# PIC.net
KiCad netlist of a schematic drawn in Altium Designer
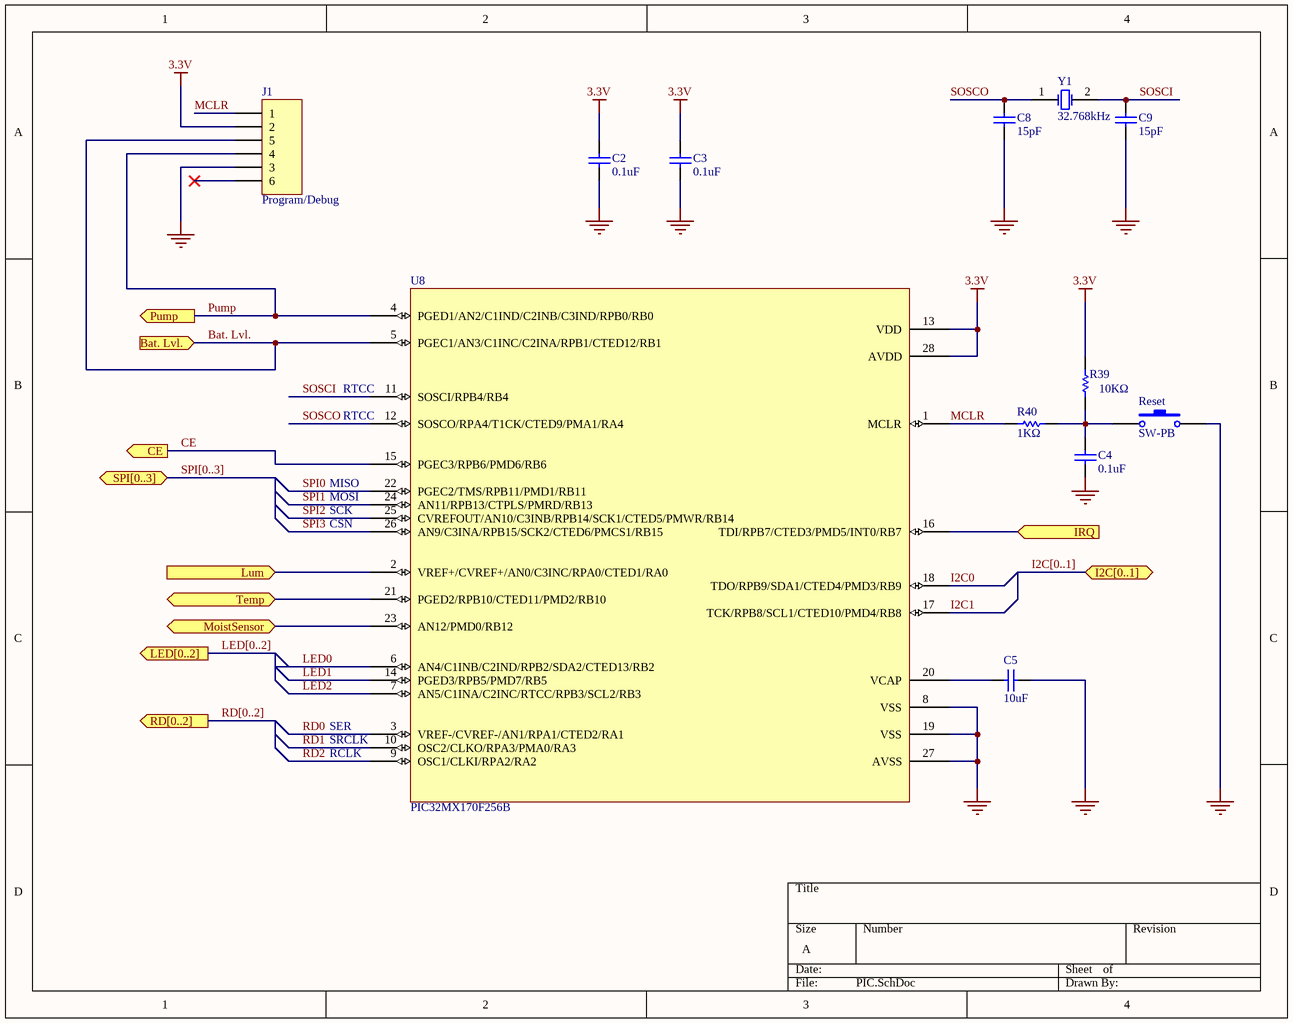
[diagram p0: PIC.SchDoc]

(export (version "E")
  (design (tool "Eeschema 10.0.6"))
  (components
    (comp (ref "C2")
      (value "0.1uF")
      (footprint "C0603")
      (description "Capacitor")
      (fields (field (name "MANUFACTURER") "MURATA") (field (name "PUBLISHER") "Altium Limited"))
      (libsource (lib "Miscellaneous Devices") (part "Cap"))
    )
    (comp (ref "C3")
      (value "0.1uF")
      (footprint "C0603")
      (description "Capacitor")
      (fields (field (name "MANUFACTURER") "MURATA") (field (name "PUBLISHER") "Altium Limited"))
      (libsource (lib "Miscellaneous Devices") (part "Cap"))
    )
    (comp (ref "C4")
      (value "0.1uF")
      (footprint "C0603")
      (description "Capacitor")
      (fields (field (name "MANUFACTURER") "MURATA") (field (name "PUBLISHER") "Altium Limited"))
      (libsource (lib "Miscellaneous Devices") (part "Cap"))
    )
    (comp (ref "C5")
      (value "10uF")
      (footprint "C0603")
      (description "Capacitor")
      (fields (field (name "MANUFACTURER") "MURATA") (field (name "PUBLISHER") "Altium Limited"))
      (libsource (lib "Miscellaneous Devices") (part "Cap"))
    )
    (comp (ref "C8")
      (value "15pF")
      (footprint "C0603")
      (description "Capacitor")
      (fields (field (name "MANUFACTURER") "MURATA") (field (name "PUBLISHER") "Altium Limited"))
      (libsource (lib "Miscellaneous Devices") (part "Cap"))
    )
    (comp (ref "C9")
      (value "15pF")
      (footprint "C0603")
      (description "Capacitor")
      (fields (field (name "MANUFACTURER") "MURATA") (field (name "PUBLISHER") "Altium Limited"))
      (libsource (lib "Miscellaneous Devices") (part "Cap"))
    )
    (comp (ref "J1")
      (value "Program/Debug")
      (footprint "HDR1X6")
      (description "Header, 6-Pin")
      (fields (field (name "PUBLISHER") "Altium Limited"))
      (libsource (lib "Miscellaneous Connectors") (part "Header 6"))
    )
    (comp (ref "R39")
      (value "10KΩ")
      (footprint "R0603")
      (description "Resistor")
      (fields (field (name "MANUFACTURER") "MULTICOMP") (field (name "PUBLISHER") "Altium Limited"))
      (libsource (lib "Miscellaneous Devices") (part "Res1"))
    )
    (comp (ref "R40")
      (value "1KΩ")
      (footprint "R0603")
      (description "Resistor")
      (fields (field (name "MANUFACTURER") "MULTICOMP") (field (name "PUBLISHER") "Altium Limited"))
      (libsource (lib "Miscellaneous Devices") (part "Res1"))
    )
    (comp (ref "Reset")
      (value "SW-PB")
      (footprint "Reset")
      (description "Switch")
      (fields
        (field (name "MANUFACTURER") "ALCOSWITCH - TE CONNECTIVITY")
        (field (name "PUBLISHER") "Altium Limited")
      )
      (libsource (lib "Miscellaneous Devices") (part "SW-PB"))
    )
    (comp (ref "U8")
      (value "PIC32MX170F256B")
      (footprint "PIC32MX170F256B")
      (description "Pic")
      (fields (field (name "MANUFACTURER") "MICROCHIP"))
      (libsource (lib "Electroplant") (part "PIC32MX170F256B"))
    )
    (comp (ref "Y1")
      (value "32.768kHz")
      (footprint "XTAL")
      (description "Crystal Oscillator")
      (fields (field (name "MANUFACTURER") "ABRACON") (field (name "PUBLISHER") "Altium Limited"))
      (libsource (lib "Miscellaneous Devices") (part "XTAL"))
    )
  )
  (nets
    (net (code "1") (name "/Bat. Lvl.") (class "Default")
      (node (ref "J1") (pin "5") (pinfunction "5_5") (pintype "passive"))
      (node (ref "U8") (pin "5") (pinfunction "PGEC1/AN3/C1INC/C2INA/RPB1/CTED12/RB1_5") (pintype "bidirectional"))
    )
    (net (code "2") (name "/CE") (class "Default")
      (node (ref "U8") (pin "15") (pinfunction "PGEC3/RPB6/PMD6/RB6_15") (pintype "bidirectional"))
    )
    (net (code "3") (name "/I2C0") (class "Default")
      (node (ref "U8") (pin "18") (pinfunction "TDO/RPB9/SDA1/CTED4/PMD3/RB9_18") (pintype "bidirectional"))
    )
    (net (code "4") (name "/I2C1") (class "Default")
      (node (ref "U8") (pin "17") (pinfunction "TCK/RPB8/SCL1/CTED10/PMD4/RB8_17") (pintype "bidirectional"))
    )
    (net (code "6") (name "/IRQ") (class "Default")
      (node (ref "U8") (pin "16") (pinfunction "TDI/RPB7/CTED3/PMD5/INT0/RB7_16") (pintype "bidirectional"))
    )
    (net (code "7") (name "/LED0") (class "Default")
      (node (ref "U8") (pin "6") (pinfunction "AN4/C1INB/C2IND/RPB2/SDA2/CTED13/RB2_6") (pintype "bidirectional"))
    )
    (net (code "8") (name "/LED1") (class "Default")
      (node (ref "U8") (pin "14") (pinfunction "PGED3/RPB5/PMD7/RB5_14") (pintype "bidirectional"))
    )
    (net (code "9") (name "/LED2") (class "Default")
      (node (ref "U8") (pin "7") (pinfunction "AN5/C1INA/C2INC/RTCC/RPB3/SCL2/RB3_7") (pintype "bidirectional"))
    )
    (net (code "11") (name "/Lum") (class "Default")
      (node (ref "U8") (pin "2") (pinfunction "VREF+/CVREF+/AN0/C3INC/RPA0/CTED1/RA0_2") (pintype "bidirectional"))
    )
    (net (code "12") (name "/MCLR") (class "Default")
      (node (ref "J1") (pin "1") (pinfunction "1_1") (pintype "passive"))
      (node (ref "R40") (pin "2") (pinfunction "2_2") (pintype "passive"))
      (node (ref "U8") (pin "1") (pinfunction "MCLR_1") (pintype "bidirectional"))
    )
    (net (code "13") (name "/MoistSensor") (class "Default")
      (node (ref "U8") (pin "23") (pinfunction "AN12/PMD0/RB12_23") (pintype "bidirectional"))
    )
    (net (code "14") (name "/Pump") (class "Default")
      (node (ref "J1") (pin "4") (pinfunction "4_4") (pintype "passive"))
      (node (ref "U8") (pin "4") (pinfunction "PGED1/AN2/C1IND/C2INB/C3IND/RPB0/RB0_4") (pintype "bidirectional"))
    )
    (net (code "15") (name "/RD0") (class "Default")
      (node (ref "U8") (pin "3") (pinfunction "VREF-/CVREF-/AN1/RPA1/CTED2/RA1_3") (pintype "bidirectional"))
    )
    (net (code "16") (name "/RD1") (class "Default")
      (node (ref "U8") (pin "10") (pinfunction "OSC2/CLKO/RPA3/PMA0/RA3_10") (pintype "bidirectional"))
    )
    (net (code "17") (name "/RD2") (class "Default")
      (node (ref "U8") (pin "9") (pinfunction "OSC1/CLKI/RPA2/RA2_9") (pintype "bidirectional"))
    )
    (net (code "19") (name "/SOSCI") (class "Default")
      (node (ref "C9") (pin "2") (pinfunction "2_2") (pintype "passive"))
      (node (ref "U8") (pin "11") (pinfunction "SOSCI/RPB4/RB4_11") (pintype "bidirectional"))
      (node (ref "Y1") (pin "2") (pinfunction "OSC2_2") (pintype "passive"))
    )
    (net (code "20") (name "/SOSCO") (class "Default")
      (node (ref "C8") (pin "2") (pinfunction "2_2") (pintype "passive"))
      (node (ref "U8") (pin "12") (pinfunction "SOSCO/RPA4/T1CK/CTED9/PMA1/RA4_12") (pintype "bidirectional"))
      (node (ref "Y1") (pin "1") (pinfunction "OSC1_1") (pintype "passive"))
    )
    (net (code "21") (name "/SPI0") (class "Default")
      (node (ref "U8") (pin "22") (pinfunction "PGEC2/TMS/RPB11/PMD1/RB11_22") (pintype "bidirectional"))
    )
    (net (code "22") (name "/SPI1") (class "Default")
      (node (ref "U8") (pin "24") (pinfunction "AN11/RPB13/CTPLS/PMRD/RB13_24") (pintype "bidirectional"))
    )
    (net (code "23") (name "/SPI2") (class "Default")
      (node (ref "U8") (pin "25") (pinfunction "CVREFOUT/AN10/C3INB/RPB14/SCK1/CTED5/PMWR/RB14_25") (pintype "bidirectional"))
    )
    (net (code "24") (name "/SPI3") (class "Default")
      (node (ref "U8") (pin "26") (pinfunction "AN9/C3INA/RPB15/SCK2/CTED6/PMCS1/RB15_26") (pintype "bidirectional"))
    )
    (net (code "26") (name "/Temp") (class "Default")
      (node (ref "U8") (pin "21") (pinfunction "PGED2/RPB10/CTED11/PMD2/RB10_21") (pintype "bidirectional"))
    )
    (net (code "27") (name "3.3V") (class "Default")
      (node (ref "C2") (pin "2") (pinfunction "2_2") (pintype "passive"))
      (node (ref "C3") (pin "2") (pinfunction "2_2") (pintype "passive"))
      (node (ref "J1") (pin "2") (pinfunction "2_2") (pintype "passive"))
      (node (ref "R39") (pin "2") (pinfunction "2_2") (pintype "passive"))
      (node (ref "U8") (pin "13") (pinfunction "VDD_13") (pintype "power_in"))
      (node (ref "U8") (pin "28") (pinfunction "AVDD_28") (pintype "power_in"))
    )
    (net (code "28") (name "GND") (class "Default")
      (node (ref "C2") (pin "1") (pinfunction "1_1") (pintype "passive"))
      (node (ref "C3") (pin "1") (pinfunction "1_1") (pintype "passive"))
      (node (ref "C4") (pin "1") (pinfunction "1_1") (pintype "passive"))
      (node (ref "C5") (pin "2") (pinfunction "2_2") (pintype "passive"))
      (node (ref "C8") (pin "1") (pinfunction "1_1") (pintype "passive"))
      (node (ref "C9") (pin "1") (pinfunction "1_1") (pintype "passive"))
      (node (ref "J1") (pin "3") (pinfunction "3_3") (pintype "passive"))
      (node (ref "Reset") (pin "2") (pinfunction "2_2") (pintype "passive"))
      (node (ref "U8") (pin "19") (pinfunction "VSS_19") (pintype "power_in"))
      (node (ref "U8") (pin "27") (pinfunction "AVSS_27") (pintype "power_in"))
      (node (ref "U8") (pin "8") (pinfunction "VSS_8") (pintype "power_in"))
    )
    (net (code "29") (name "Net-(C4-Pad2)") (class "Default")
      (node (ref "C4") (pin "2") (pinfunction "2_2") (pintype "passive"))
      (node (ref "R39") (pin "1") (pinfunction "1_1") (pintype "passive"))
      (node (ref "R40") (pin "1") (pinfunction "1_1") (pintype "passive"))
      (node (ref "Reset") (pin "1") (pinfunction "1_1") (pintype "passive"))
    )
    (net (code "30") (name "Net-(U8-VCAP)") (class "Default")
      (node (ref "C5") (pin "1") (pinfunction "1_1") (pintype "passive"))
      (node (ref "U8") (pin "20") (pinfunction "VCAP_20") (pintype "power_in"))
    )
    (net (code "31") (name "unconnected-(J1-Pad6)") (class "Default")
      (node (ref "J1") (pin "6") (pinfunction "6_6") (pintype "passive+no_connect"))
    )
  )
)
